# emmeteur.net
KiCad netlist of a schematic drawn in Altium Designer
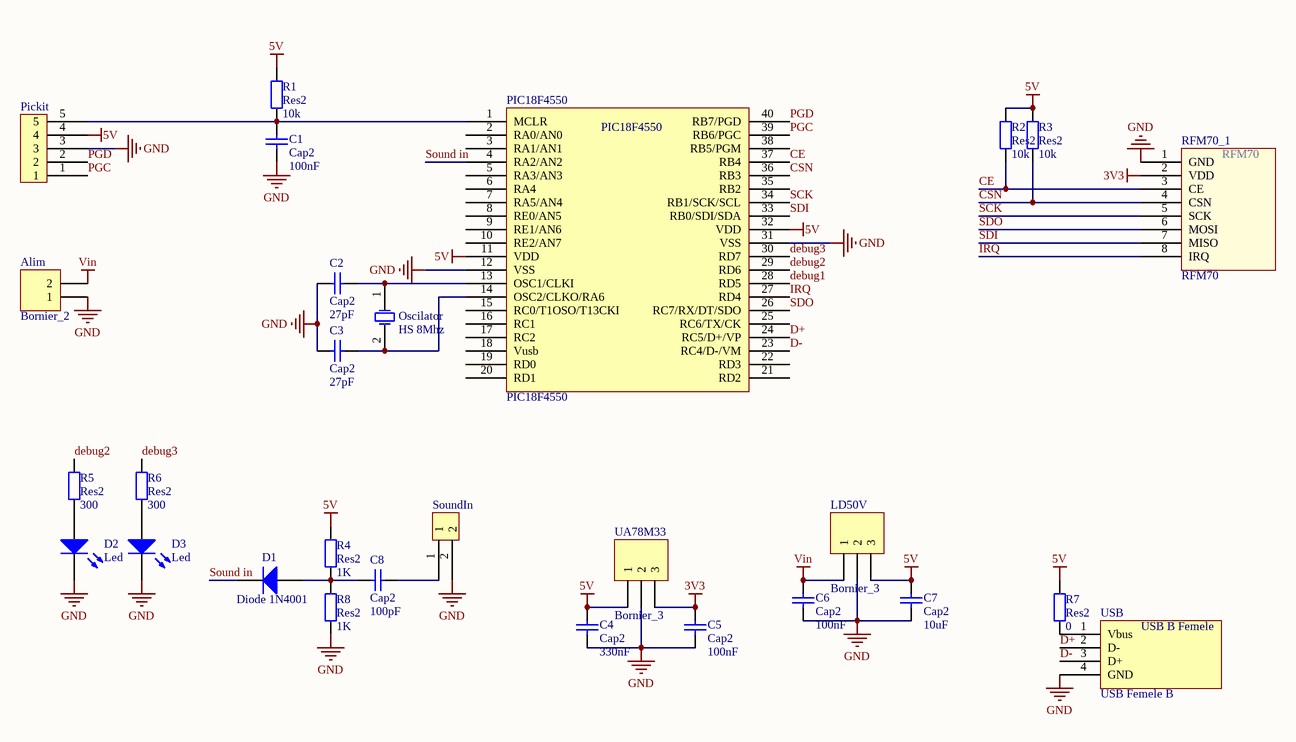
[diagram p0: emmeteur.SchDoc]

(export (version "E")
  (design (tool "Eeschema 10.0.6"))
  (components
    (comp (ref "Alim")
      (value "Bornier_2")
      (footprint "Bornier_2")
      (description "Header, 2-Pin")
      (fields (field (name "PUBLISHER") "Altium Limited"))
      (libsource (lib "INTEGRATED_LIBRARY1_CONNECTEURS") (part "Bornier_2"))
    )
    (comp (ref "C1")
      (value "Cap2")
      (footprint "CAPA2")
      (description "Capacitor")
      (fields (field (name "ALTIUM_VALUE") "100nF") (field (name "PUBLISHER") "Altium Limited"))
      (libsource (lib "LIBRAIRIE_INTEGREE_PHELMA1") (part "Cap2"))
    )
    (comp (ref "C2")
      (value "Cap2")
      (footprint "CAPA2")
      (description "Capacitor")
      (fields (field (name "ALTIUM_VALUE") "27pF") (field (name "PUBLISHER") "Altium Limited"))
      (libsource (lib "LIBRAIRIE_INTEGREE_PHELMA1") (part "Cap2"))
    )
    (comp (ref "C3")
      (value "Cap2")
      (footprint "CAPA2")
      (description "Capacitor")
      (fields (field (name "ALTIUM_VALUE") "27pF") (field (name "PUBLISHER") "Altium Limited"))
      (libsource (lib "LIBRAIRIE_INTEGREE_PHELMA1") (part "Cap2"))
    )
    (comp (ref "C4")
      (value "Cap2")
      (footprint "CAPA2")
      (description "Capacitor")
      (fields (field (name "ALTIUM_VALUE") "330nF") (field (name "PUBLISHER") "Altium Limited"))
      (libsource (lib "LIBRAIRIE_INTEGREE_PHELMA1") (part "Cap2"))
    )
    (comp (ref "C5")
      (value "Cap2")
      (footprint "CAPA2")
      (description "Capacitor")
      (fields (field (name "ALTIUM_VALUE") "100nF") (field (name "PUBLISHER") "Altium Limited"))
      (libsource (lib "LIBRAIRIE_INTEGREE_PHELMA1") (part "Cap2"))
    )
    (comp (ref "C6")
      (value "Cap2")
      (footprint "CAPA2")
      (description "Capacitor")
      (fields (field (name "ALTIUM_VALUE") "100nF") (field (name "PUBLISHER") "Altium Limited"))
      (libsource (lib "LIBRAIRIE_INTEGREE_PHELMA1") (part "Cap2"))
    )
    (comp (ref "C7")
      (value "Cap2")
      (footprint "CAPA2")
      (description "Capacitor")
      (fields (field (name "ALTIUM_VALUE") "10uF") (field (name "PUBLISHER") "Altium Limited"))
      (libsource (lib "LIBRAIRIE_INTEGREE_PHELMA1") (part "Cap2"))
    )
    (comp (ref "C8")
      (value "Cap2")
      (footprint "CAPA2")
      (description "Capacitor")
      (fields (field (name "ALTIUM_VALUE") "100pF") (field (name "PUBLISHER") "Altium Limited"))
      (libsource (lib "LIBRAIRIE_INTEGREE_PHELMA1") (part "Cap2"))
    )
    (comp (ref "D1")
      (value "Diode 1N4001")
      (footprint "Ddiode")
      (description "1 Amp General Purpose Rectifier")
      (fields (field (name "PUBLISHER") "Altium Limited"))
      (libsource (lib "LIBRAIRIE_INTEGREE_PHELMA1") (part "Diode 1N4001"))
    )
    (comp (ref "D2")
      (value "Led")
      (footprint "LED")
      (description "LED")
      (fields (field (name "PUBLISHER") "Altium Limited"))
      (libsource (lib "LIBRAIRIE_INTEGREE_PHELMA1") (part "Led"))
    )
    (comp (ref "D3")
      (value "Led")
      (footprint "LED")
      (description "LED")
      (fields (field (name "PUBLISHER") "Altium Limited"))
      (libsource (lib "LIBRAIRIE_INTEGREE_PHELMA1") (part "Led"))
    )
    (comp (ref "LD50V")
      (value "Bornier_3")
      (footprint "Bornier_3")
      (description "Header, 3-Pin")
      (fields (field (name "PUBLISHER") "Altium Limited"))
      (libsource (lib "INTEGRATED_LIBRARY1_CONNECTEURS") (part "Bornier_3"))
    )
    (comp (ref "Oscilator")
      (value "HS 8Mhz")
      (footprint "R38")
      (description "Crystal Oscillator")
      (fields (field (name "PUBLISHER") "Altium Limited"))
      (libsource (lib "Miscellaneous Devices") (part "XTAL"))
    )
    (comp (ref "PIC18F4550")
      (value "PIC18F4550")
      (footprint "pic18F4550 - duplicate")
      (libsource (lib "pic") (part "PIC18F4550"))
    )
    (comp (ref "Pickit")
      (value "CONKK5")
      (footprint "CONKK5")
      (libsource (lib "INTEGRATED_LIBRARY1_CONNECTEURS") (part "CONKK5"))
    )
    (comp (ref "R1")
      (value "Res2")
      (footprint "res5_1/4W")
      (description "Resistor")
      (fields (field (name "ALTIUM_VALUE") "10k") (field (name "PUBLISHER") "Altium Limited"))
      (libsource (lib "LIBRAIRIE_INTEGREE_PHELMA1") (part "Res2"))
    )
    (comp (ref "R2")
      (value "Res2")
      (footprint "res5_1/4W")
      (description "Resistor")
      (fields (field (name "ALTIUM_VALUE") "10k") (field (name "PUBLISHER") "Altium Limited"))
      (libsource (lib "LIBRAIRIE_INTEGREE_PHELMA1") (part "Res2"))
    )
    (comp (ref "R3")
      (value "Res2")
      (footprint "res5_1/4W")
      (description "Resistor")
      (fields (field (name "ALTIUM_VALUE") "10k") (field (name "PUBLISHER") "Altium Limited"))
      (libsource (lib "LIBRAIRIE_INTEGREE_PHELMA1") (part "Res2"))
    )
    (comp (ref "R4")
      (value "Res2")
      (footprint "res5_1/4W")
      (description "Resistor")
      (fields (field (name "ALTIUM_VALUE") "1K") (field (name "PUBLISHER") "Altium Limited"))
      (libsource (lib "LIBRAIRIE_INTEGREE_PHELMA1") (part "Res2"))
    )
    (comp (ref "R5")
      (value "Res2")
      (footprint "res5_1/4W")
      (description "Resistor")
      (fields (field (name "ALTIUM_VALUE") "300") (field (name "PUBLISHER") "Altium Limited"))
      (libsource (lib "LIBRAIRIE_INTEGREE_PHELMA1") (part "Res2"))
    )
    (comp (ref "R6")
      (value "Res2")
      (footprint "res5_1/4W")
      (description "Resistor")
      (fields (field (name "ALTIUM_VALUE") "300") (field (name "PUBLISHER") "Altium Limited"))
      (libsource (lib "LIBRAIRIE_INTEGREE_PHELMA1") (part "Res2"))
    )
    (comp (ref "R7")
      (value "Res2")
      (footprint "res5_1/4W")
      (description "Resistor")
      (fields (field (name "ALTIUM_VALUE") "0") (field (name "PUBLISHER") "Altium Limited"))
      (libsource (lib "LIBRAIRIE_INTEGREE_PHELMA1") (part "Res2"))
    )
    (comp (ref "R8")
      (value "Res2")
      (footprint "res5_1/4W")
      (description "Resistor")
      (fields (field (name "ALTIUM_VALUE") "1K") (field (name "PUBLISHER") "Altium Limited"))
      (libsource (lib "LIBRAIRIE_INTEGREE_PHELMA1") (part "Res2"))
    )
    (comp (ref "RFM70_1") (value "RFM70") (footprint "RFM70") (libsource (lib "pic") (part "RFM70")))
    (comp (ref "SoundIn")
      (value "CONKK2")
      (footprint "CONKK2")
      (libsource (lib "INTEGRATED_LIBRARY1_CONNECTEURS") (part "CONKK2"))
    )
    (comp (ref "UA78M33")
      (value "Bornier_3")
      (footprint "Bornier_3")
      (description "Header, 3-Pin")
      (fields (field (name "PUBLISHER") "Altium Limited"))
      (libsource (lib "INTEGRATED_LIBRARY1_CONNECTEURS") (part "Bornier_3"))
    )
    (comp (ref "USB")
      (value "USB Femele B")
      (footprint "USB-B")
      (libsource (lib "pic") (part "USB Femele B"))
    )
  )
  (nets
    (net (code "1") (name "/CE") (class "Default")
      (node (ref "PIC18F4550") (pin "37") (pinfunction "RB4_37") (pintype "passive"))
      (node (ref "R2") (pin "1") (pinfunction "1_1") (pintype "passive"))
      (node (ref "RFM70_1") (pin "3") (pinfunction "CE_3") (pintype "passive"))
    )
    (net (code "2") (name "/CSN") (class "Default")
      (node (ref "PIC18F4550") (pin "36") (pinfunction "RB3_36") (pintype "passive"))
      (node (ref "R3") (pin "1") (pinfunction "1_1") (pintype "passive"))
      (node (ref "RFM70_1") (pin "4") (pinfunction "CSN_4") (pintype "passive"))
    )
    (net (code "3") (name "/D+") (class "Default")
      (node (ref "PIC18F4550") (pin "24") (pinfunction "RC5/D+/VP_24") (pintype "passive"))
      (node (ref "USB") (pin "2") (pinfunction "D-_2") (pintype "passive"))
    )
    (net (code "4") (name "/D-") (class "Default")
      (node (ref "PIC18F4550") (pin "23") (pinfunction "RC4/D-/VM_23") (pintype "passive"))
      (node (ref "USB") (pin "3") (pinfunction "D+_3") (pintype "passive"))
    )
    (net (code "5") (name "/IRQ") (class "Default")
      (node (ref "PIC18F4550") (pin "27") (pinfunction "RD4_27") (pintype "passive"))
      (node (ref "RFM70_1") (pin "8") (pinfunction "IRQ_8") (pintype "passive"))
    )
    (net (code "6") (name "/PGC") (class "Default")
      (node (ref "PIC18F4550") (pin "39") (pinfunction "RB6/PGC_39") (pintype "passive"))
      (node (ref "Pickit") (pin "1") (pinfunction "1_1") (pintype "passive"))
    )
    (net (code "7") (name "/PGD") (class "Default")
      (node (ref "PIC18F4550") (pin "40") (pinfunction "RB7/PGD_40") (pintype "passive"))
      (node (ref "Pickit") (pin "2") (pinfunction "2_2") (pintype "passive"))
    )
    (net (code "8") (name "/SCK") (class "Default")
      (node (ref "PIC18F4550") (pin "34") (pinfunction "RB1/SCK/SCL_34") (pintype "passive"))
      (node (ref "RFM70_1") (pin "5") (pinfunction "SCK_5") (pintype "passive"))
    )
    (net (code "9") (name "/SDI") (class "Default")
      (node (ref "PIC18F4550") (pin "33") (pinfunction "RB0/SDI/SDA_33") (pintype "passive"))
      (node (ref "RFM70_1") (pin "7") (pinfunction "MISO_7") (pintype "passive"))
    )
    (net (code "10") (name "/SDO") (class "Default")
      (node (ref "PIC18F4550") (pin "26") (pinfunction "RC7/RX/DT/SDO_26") (pintype "passive"))
      (node (ref "RFM70_1") (pin "6") (pinfunction "MOSI_6") (pintype "passive"))
    )
    (net (code "11") (name "/Sound in") (class "Default")
      (node (ref "D1") (pin "2") (pinfunction "K_2") (pintype "passive"))
      (node (ref "PIC18F4550") (pin "4") (pinfunction "RA2/AN2_4") (pintype "passive"))
    )
    (net (code "12") (name "/debug1") (class "Default")
      (node (ref "PIC18F4550") (pin "28") (pinfunction "RD5_28") (pintype "passive"))
    )
    (net (code "13") (name "/debug2") (class "Default")
      (node (ref "PIC18F4550") (pin "29") (pinfunction "RD6_29") (pintype "passive"))
      (node (ref "R5") (pin "2") (pinfunction "2_2") (pintype "passive"))
    )
    (net (code "14") (name "/debug3") (class "Default")
      (node (ref "PIC18F4550") (pin "30") (pinfunction "RD7_30") (pintype "passive"))
      (node (ref "R6") (pin "2") (pinfunction "2_2") (pintype "passive"))
    )
    (net (code "15") (name "3V3") (class "Default")
      (node (ref "C5") (pin "2") (pinfunction "2_2") (pintype "passive"))
      (node (ref "RFM70_1") (pin "2") (pinfunction "VDD_2") (pintype "passive"))
      (node (ref "UA78M33") (pin "3") (pinfunction "3_3") (pintype "passive"))
    )
    (net (code "16") (name "5V") (class "Default")
      (node (ref "C4") (pin "2") (pinfunction "2_2") (pintype "passive"))
      (node (ref "C7") (pin "2") (pinfunction "2_2") (pintype "passive"))
      (node (ref "LD50V") (pin "3") (pinfunction "3_3") (pintype "passive"))
      (node (ref "PIC18F4550") (pin "11") (pinfunction "VDD_11") (pintype "passive"))
      (node (ref "PIC18F4550") (pin "32") (pinfunction "VDD_32") (pintype "passive"))
      (node (ref "Pickit") (pin "4") (pinfunction "4_4") (pintype "passive"))
      (node (ref "R1") (pin "2") (pinfunction "2_2") (pintype "passive"))
      (node (ref "R2") (pin "2") (pinfunction "2_2") (pintype "passive"))
      (node (ref "R3") (pin "2") (pinfunction "2_2") (pintype "passive"))
      (node (ref "R4") (pin "2") (pinfunction "2_2") (pintype "passive"))
      (node (ref "R7") (pin "2") (pinfunction "2_2") (pintype "passive"))
      (node (ref "UA78M33") (pin "1") (pinfunction "1_1") (pintype "passive"))
    )
    (net (code "17") (name "GND") (class "Default")
      (node (ref "Alim") (pin "1") (pinfunction "1_1") (pintype "passive"))
      (node (ref "C1") (pin "1") (pinfunction "1_1") (pintype "passive"))
      (node (ref "C2") (pin "1") (pinfunction "1_1") (pintype "passive"))
      (node (ref "C3") (pin "1") (pinfunction "1_1") (pintype "passive"))
      (node (ref "C4") (pin "1") (pinfunction "1_1") (pintype "passive"))
      (node (ref "C5") (pin "1") (pinfunction "1_1") (pintype "passive"))
      (node (ref "C6") (pin "1") (pinfunction "1_1") (pintype "passive"))
      (node (ref "C7") (pin "1") (pinfunction "1_1") (pintype "passive"))
      (node (ref "D2") (pin "2") (pinfunction "K_2") (pintype "passive"))
      (node (ref "D3") (pin "2") (pinfunction "K_2") (pintype "passive"))
      (node (ref "LD50V") (pin "2") (pinfunction "2_2") (pintype "passive"))
      (node (ref "PIC18F4550") (pin "12") (pinfunction "VSS_12") (pintype "passive"))
      (node (ref "PIC18F4550") (pin "31") (pinfunction "VSS_31") (pintype "passive"))
      (node (ref "Pickit") (pin "3") (pinfunction "3_3") (pintype "passive"))
      (node (ref "R8") (pin "1") (pinfunction "1_1") (pintype "passive"))
      (node (ref "RFM70_1") (pin "1") (pinfunction "GND_1") (pintype "passive"))
      (node (ref "SoundIn") (pin "2") (pinfunction "2_2") (pintype "passive"))
      (node (ref "UA78M33") (pin "2") (pinfunction "2_2") (pintype "passive"))
      (node (ref "USB") (pin "4") (pinfunction "GND_4") (pintype "passive"))
    )
    (net (code "18") (name "Net-(C8-Pad2)") (class "Default")
      (node (ref "C8") (pin "2") (pinfunction "2_2") (pintype "passive"))
      (node (ref "SoundIn") (pin "1") (pinfunction "1_1") (pintype "passive"))
    )
    (net (code "19") (name "Net-(D1-A)") (class "Default")
      (node (ref "C8") (pin "1") (pinfunction "1_1") (pintype "passive"))
      (node (ref "D1") (pin "1") (pinfunction "A_1") (pintype "passive"))
      (node (ref "R4") (pin "1") (pinfunction "1_1") (pintype "passive"))
      (node (ref "R8") (pin "2") (pinfunction "2_2") (pintype "passive"))
    )
    (net (code "20") (name "Net-(D2-A)") (class "Default")
      (node (ref "D2") (pin "1") (pinfunction "A_1") (pintype "passive"))
      (node (ref "R5") (pin "1") (pinfunction "1_1") (pintype "passive"))
    )
    (net (code "21") (name "Net-(D3-A)") (class "Default")
      (node (ref "D3") (pin "1") (pinfunction "A_1") (pintype "passive"))
      (node (ref "R6") (pin "1") (pinfunction "1_1") (pintype "passive"))
    )
    (net (code "22") (name "Net-(Oscilator-OSC1)") (class "Default")
      (node (ref "C2") (pin "2") (pinfunction "2_2") (pintype "passive"))
      (node (ref "Oscilator") (pin "1") (pinfunction "OSC1_1") (pintype "passive"))
      (node (ref "PIC18F4550") (pin "13") (pinfunction "OSC1/CLKI_13") (pintype "passive"))
    )
    (net (code "23") (name "Net-(Oscilator-OSC2)") (class "Default")
      (node (ref "C3") (pin "2") (pinfunction "2_2") (pintype "passive"))
      (node (ref "Oscilator") (pin "2") (pinfunction "OSC2_2") (pintype "passive"))
      (node (ref "PIC18F4550") (pin "14") (pinfunction "OSC2/CLKO/RA6_14") (pintype "passive"))
    )
    (net (code "24") (name "Net-(PIC18F4550-MCLR)") (class "Default")
      (node (ref "C1") (pin "2") (pinfunction "2_2") (pintype "passive"))
      (node (ref "PIC18F4550") (pin "1") (pinfunction "MCLR_1") (pintype "passive"))
      (node (ref "Pickit") (pin "5") (pinfunction "5_5") (pintype "passive"))
      (node (ref "R1") (pin "1") (pinfunction "1_1") (pintype "passive"))
    )
    (net (code "25") (name "Net-(USB-Vbus)") (class "Default")
      (node (ref "R7") (pin "1") (pinfunction "1_1") (pintype "passive"))
      (node (ref "USB") (pin "1") (pinfunction "Vbus_1") (pintype "passive"))
    )
    (net (code "26") (name "Vin") (class "Default")
      (node (ref "Alim") (pin "2") (pinfunction "2_2") (pintype "passive"))
      (node (ref "C6") (pin "2") (pinfunction "2_2") (pintype "passive"))
      (node (ref "LD50V") (pin "1") (pinfunction "1_1") (pintype "passive"))
    )
    (net (code "27") (name "unconnected-(PIC18F4550-RA0{slash}AN0-Pad2)") (class "Default")
      (node (ref "PIC18F4550") (pin "2") (pinfunction "RA0/AN0_2") (pintype "passive"))
    )
    (net (code "28") (name "unconnected-(PIC18F4550-RA1{slash}AN1-Pad3)") (class "Default")
      (node (ref "PIC18F4550") (pin "3") (pinfunction "RA1/AN1_3") (pintype "passive"))
    )
    (net (code "29") (name "unconnected-(PIC18F4550-RA3{slash}AN3-Pad5)") (class "Default")
      (node (ref "PIC18F4550") (pin "5") (pinfunction "RA3/AN3_5") (pintype "passive"))
    )
    (net (code "30") (name "unconnected-(PIC18F4550-RA4-Pad6)") (class "Default")
      (node (ref "PIC18F4550") (pin "6") (pinfunction "RA4_6") (pintype "passive"))
    )
    (net (code "31") (name "unconnected-(PIC18F4550-RA5{slash}AN4-Pad7)") (class "Default")
      (node (ref "PIC18F4550") (pin "7") (pinfunction "RA5/AN4_7") (pintype "passive"))
    )
    (net (code "32") (name "unconnected-(PIC18F4550-RB2-Pad35)") (class "Default")
      (node (ref "PIC18F4550") (pin "35") (pinfunction "RB2_35") (pintype "passive"))
    )
    (net (code "33") (name "unconnected-(PIC18F4550-RB5{slash}PGM-Pad38)") (class "Default")
      (node (ref "PIC18F4550") (pin "38") (pinfunction "RB5/PGM_38") (pintype "passive"))
    )
    (net (code "34") (name "unconnected-(PIC18F4550-RC0{slash}T1OSO{slash}T13CKI-Pad15)") (class "Default")
      (node (ref "PIC18F4550") (pin "15") (pinfunction "RC0/T1OSO/T13CKI_15") (pintype "passive"))
    )
    (net (code "35") (name "unconnected-(PIC18F4550-RC1-Pad16)") (class "Default")
      (node (ref "PIC18F4550") (pin "16") (pinfunction "RC1_16") (pintype "passive"))
    )
    (net (code "36") (name "unconnected-(PIC18F4550-RC2-Pad17)") (class "Default")
      (node (ref "PIC18F4550") (pin "17") (pinfunction "RC2_17") (pintype "passive"))
    )
    (net (code "37") (name "unconnected-(PIC18F4550-RC6{slash}TX{slash}CK-Pad25)") (class "Default")
      (node (ref "PIC18F4550") (pin "25") (pinfunction "RC6/TX/CK_25") (pintype "passive"))
    )
    (net (code "38") (name "unconnected-(PIC18F4550-RD0-Pad19)") (class "Default")
      (node (ref "PIC18F4550") (pin "19") (pinfunction "RD0_19") (pintype "passive"))
    )
    (net (code "39") (name "unconnected-(PIC18F4550-RD1-Pad20)") (class "Default")
      (node (ref "PIC18F4550") (pin "20") (pinfunction "RD1_20") (pintype "passive"))
    )
    (net (code "40") (name "unconnected-(PIC18F4550-RD2-Pad21)") (class "Default")
      (node (ref "PIC18F4550") (pin "21") (pinfunction "RD2_21") (pintype "passive"))
    )
    (net (code "41") (name "unconnected-(PIC18F4550-RD3-Pad22)") (class "Default")
      (node (ref "PIC18F4550") (pin "22") (pinfunction "RD3_22") (pintype "passive"))
    )
    (net (code "42") (name "unconnected-(PIC18F4550-RE0{slash}AN5-Pad8)") (class "Default")
      (node (ref "PIC18F4550") (pin "8") (pinfunction "RE0/AN5_8") (pintype "passive"))
    )
    (net (code "43") (name "unconnected-(PIC18F4550-RE1{slash}AN6-Pad9)") (class "Default")
      (node (ref "PIC18F4550") (pin "9") (pinfunction "RE1/AN6_9") (pintype "passive"))
    )
    (net (code "44") (name "unconnected-(PIC18F4550-RE2{slash}AN7-Pad10)") (class "Default")
      (node (ref "PIC18F4550") (pin "10") (pinfunction "RE2/AN7_10") (pintype "passive"))
    )
    (net (code "45") (name "unconnected-(PIC18F4550-Vusb-Pad18)") (class "Default")
      (node (ref "PIC18F4550") (pin "18") (pinfunction "Vusb_18") (pintype "passive"))
    )
  )
)
